# HB-WDS100-C6-O-2_WindDir_v1p0.net
KiCad netlist of a schematic drawn in EAGLE
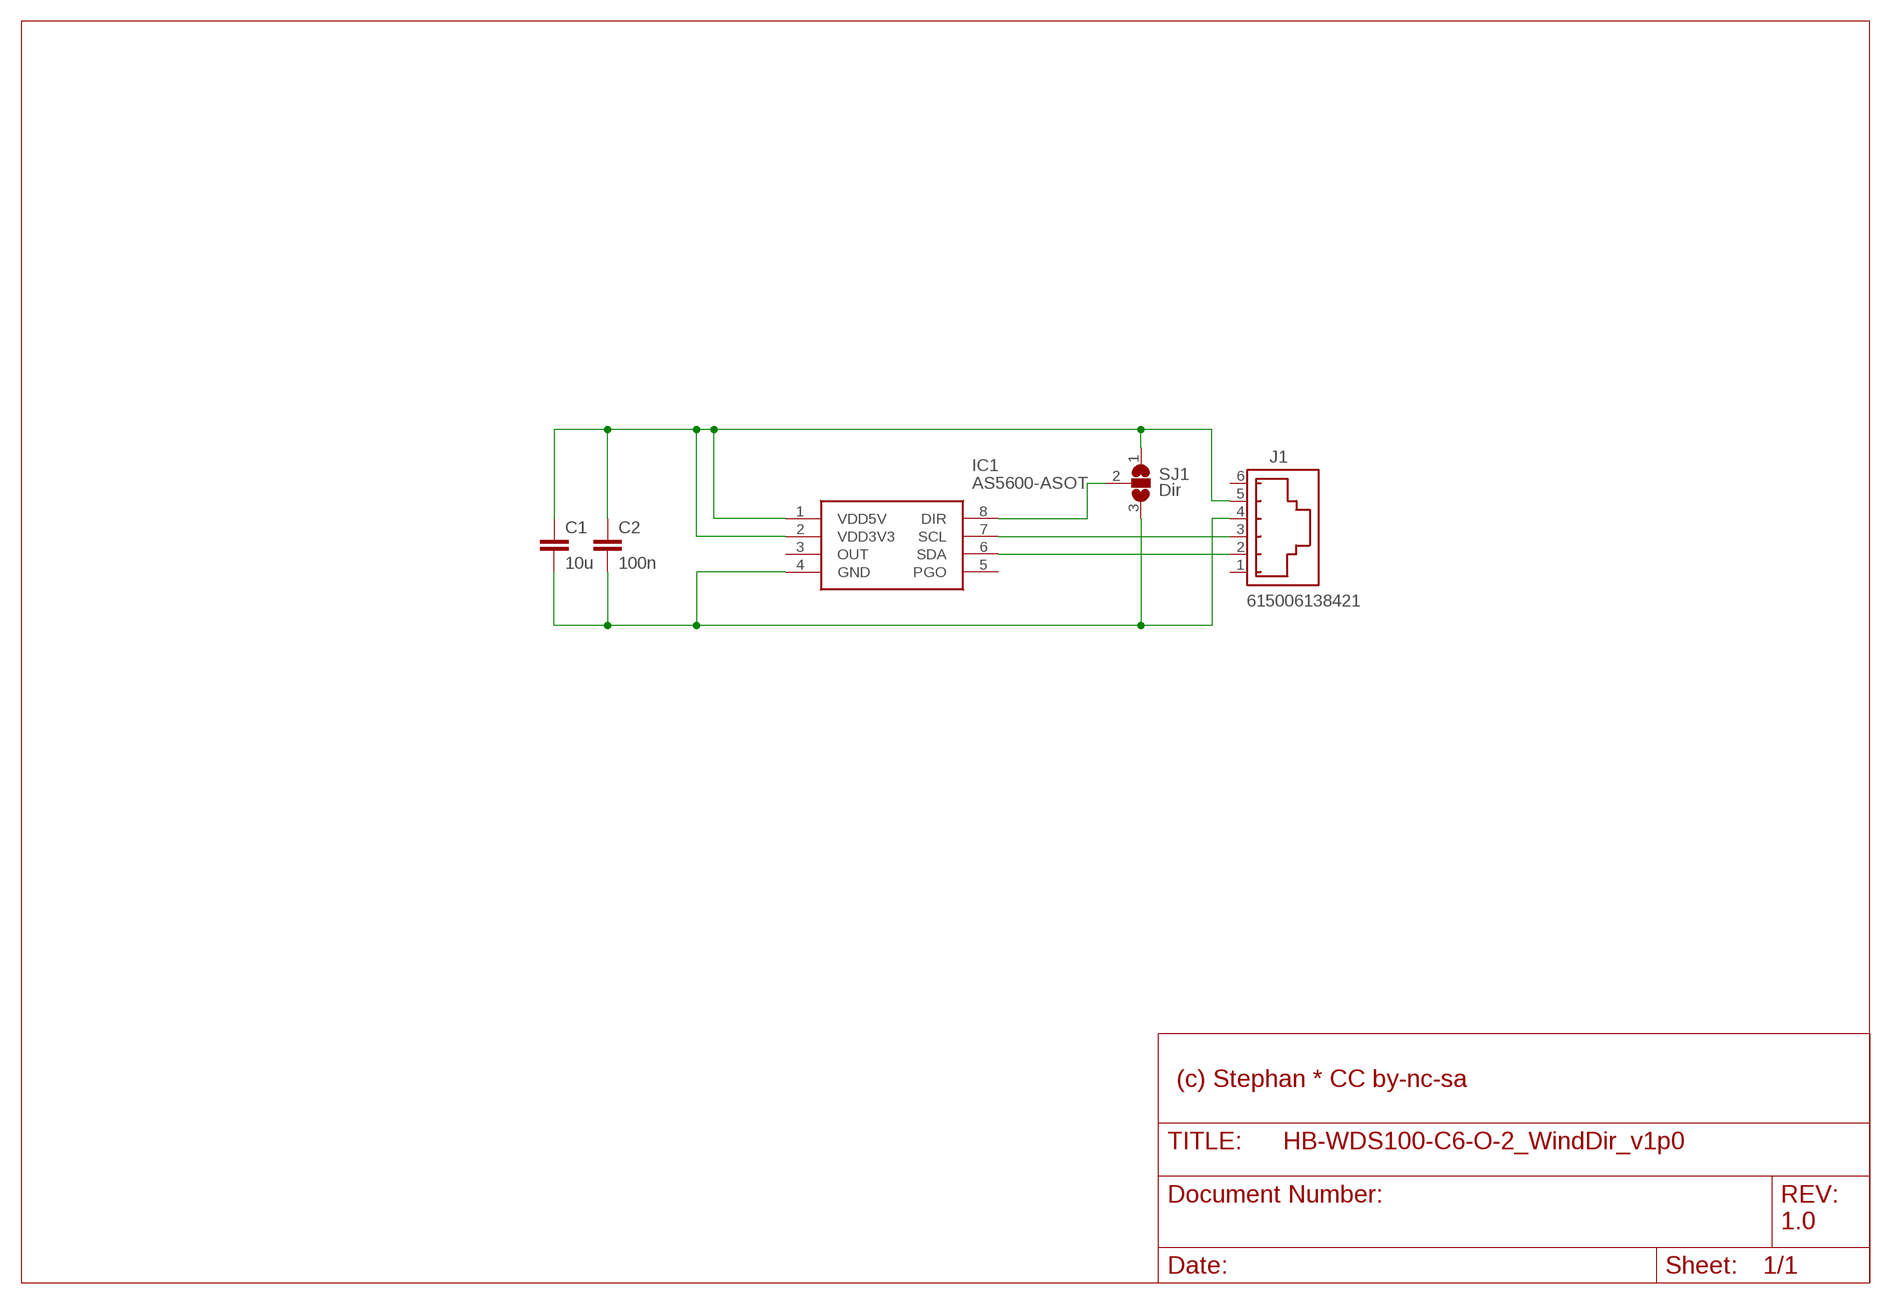
[diagram p0: schematic, sheet 1]

(export (version "E")
  (design (tool "Eeschema 10.0.6"))
  (components
    (comp (ref "C1")
      (value "10u")
      (footprint "eagle-import:C0805K")
      (libsource (lib "eagle-import") (part "C-EUC0805K"))
    )
    (comp (ref "C2")
      (value "100n")
      (footprint "eagle-import:C0805K")
      (libsource (lib "eagle-import") (part "C-EUC0805K"))
    )
    (comp (ref "IC1")
      (value "AS5600-ASOT")
      (footprint "eagle-import:SOIC127P600X175-8N")
      (fields (field (name "MOUSER_PART_NUMBER") "985-AS5600-ASOT"))
      (libsource (lib "eagle-import") (part "AS5600-ASOT"))
    )
    (comp (ref "J1")
      (value "615006138421")
      (footprint "eagle-import:615006138421")
      (libsource (lib "eagle-import") (part "615006138421"))
    )
    (comp (ref "SJ1")
      (value "Dir")
      (footprint "eagle-import:SJ_2")
      (libsource (lib "eagle-import") (part "SJ2W"))
    )
  )
  (nets
    (net (code "1") (name "Net-(IC1-DIR)") (class "Default")
      (node (ref "IC1") (pin "8") (pinfunction "DIR_8") (pintype "bidirectional"))
      (node (ref "SJ1") (pin "2") (pinfunction "2_2") (pintype "passive"))
    )
    (net (code "2") (name "Net-(IC1-GND)") (class "Default")
      (node (ref "C1") (pin "2") (pinfunction "2_2") (pintype "passive"))
      (node (ref "C2") (pin "2") (pinfunction "2_2") (pintype "passive"))
      (node (ref "IC1") (pin "4") (pinfunction "GND_4") (pintype "bidirectional"))
      (node (ref "J1") (pin "4") (pinfunction "4_4") (pintype "passive"))
      (node (ref "SJ1") (pin "3") (pinfunction "3_3") (pintype "passive"))
    )
    (net (code "3") (name "Net-(IC1-SCL)") (class "Default")
      (node (ref "IC1") (pin "7") (pinfunction "SCL_7") (pintype "bidirectional"))
      (node (ref "J1") (pin "3") (pinfunction "3_3") (pintype "passive"))
    )
    (net (code "4") (name "Net-(IC1-SDA)") (class "Default")
      (node (ref "IC1") (pin "6") (pinfunction "SDA_6") (pintype "bidirectional"))
      (node (ref "J1") (pin "2") (pinfunction "2_2") (pintype "passive"))
    )
    (net (code "5") (name "Net-(IC1-VDD3V3)") (class "Default")
      (node (ref "C1") (pin "1") (pinfunction "1_1") (pintype "passive"))
      (node (ref "C2") (pin "1") (pinfunction "1_1") (pintype "passive"))
      (node (ref "IC1") (pin "1") (pinfunction "VDD5V_1") (pintype "bidirectional"))
      (node (ref "IC1") (pin "2") (pinfunction "VDD3V3_2") (pintype "bidirectional"))
      (node (ref "J1") (pin "5") (pinfunction "5_5") (pintype "passive"))
      (node (ref "SJ1") (pin "1") (pinfunction "1_1") (pintype "passive"))
    )
    (net (code "6") (name "unconnected-(IC1-OUT-Pad3)") (class "Default")
      (node (ref "IC1") (pin "3") (pinfunction "OUT_3") (pintype "bidirectional"))
    )
    (net (code "7") (name "unconnected-(IC1-PGO-Pad5)") (class "Default")
      (node (ref "IC1") (pin "5") (pinfunction "PGO_5") (pintype "bidirectional"))
    )
    (net (code "8") (name "unconnected-(J1-Pad1)") (class "Default")
      (node (ref "J1") (pin "1") (pinfunction "1_1") (pintype "passive"))
    )
    (net (code "9") (name "unconnected-(J1-Pad6)") (class "Default")
      (node (ref "J1") (pin "6") (pinfunction "6_6") (pintype "passive"))
    )
  )
)
